# Zio_Qwiic_IO_Expander.net
KiCad netlist of a schematic drawn in EAGLE
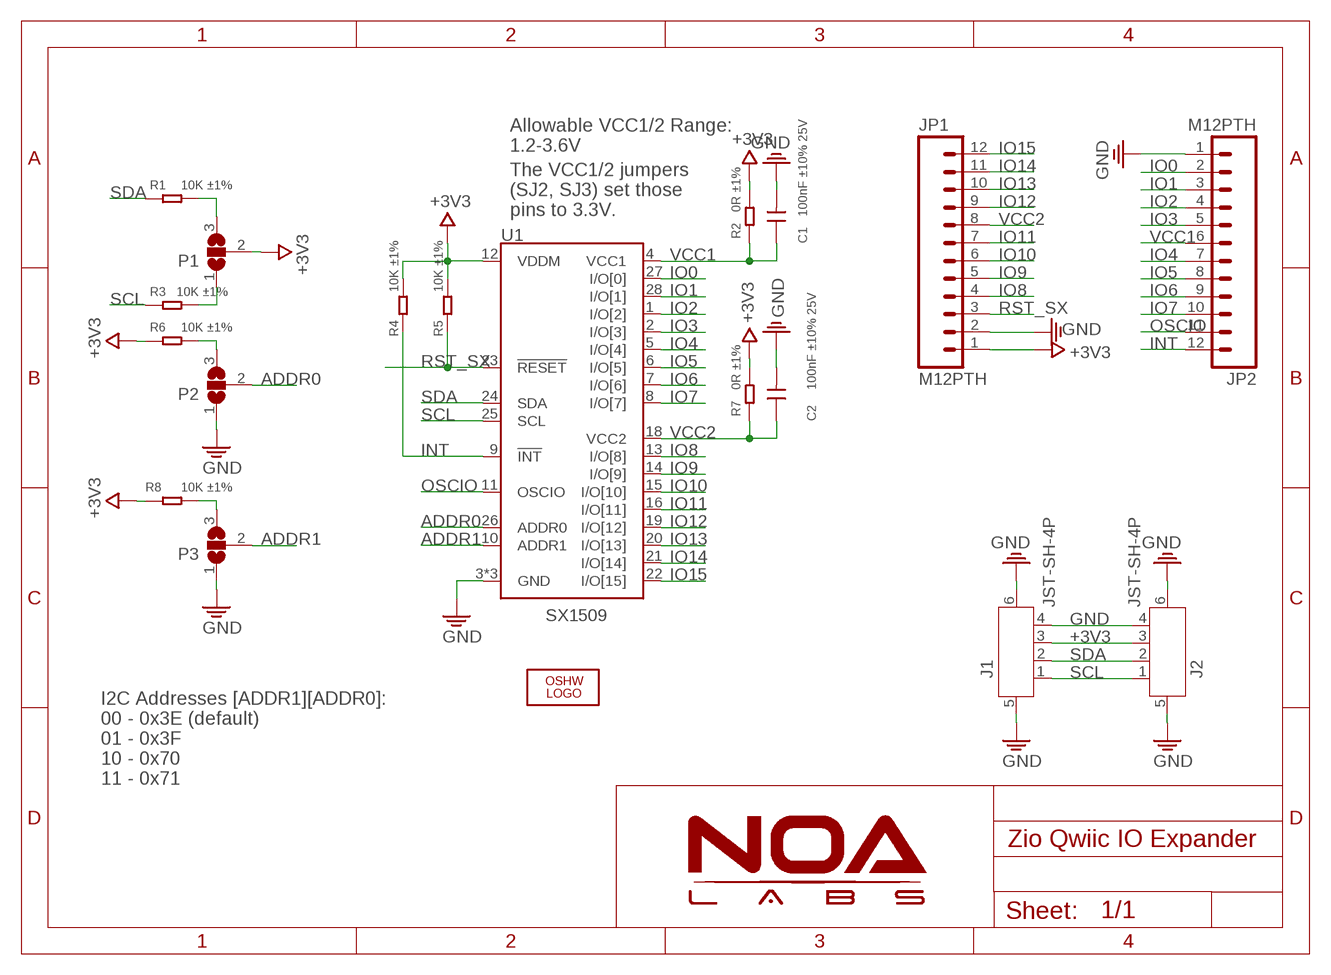
[diagram p0: schematic, sheet 1]

(export (version "E")
  (design (tool "Eeschema 10.0.6"))
  (components
    (comp (ref "C1")
      (value "100nF ±10% 25V")
      (footprint "eagle-import:0402")
      (libsource (lib "eagle-import") (part "C-0402"))
    )
    (comp (ref "C2")
      (value "100nF ±10% 25V")
      (footprint "eagle-import:0402")
      (libsource (lib "eagle-import") (part "C-0402"))
    )
    (comp (ref "J1")
      (value "JST-SH-4P")
      (footprint "eagle-import:JST-SH-4P-90")
      (libsource (lib "eagle-import") (part "JST-SH-4P"))
    )
    (comp (ref "J2")
      (value "JST-SH-4P")
      (footprint "eagle-import:JST-SH-4P-90")
      (libsource (lib "eagle-import") (part "JST-SH-4P"))
    )
    (comp (ref "JP1")
      (value "M12PTH")
      (footprint "eagle-import:1X12")
      (libsource (lib "eagle-import") (part "M12PTH"))
    )
    (comp (ref "JP2")
      (value "M12PTH")
      (footprint "eagle-import:1X12")
      (libsource (lib "eagle-import") (part "M12PTH"))
    )
    (comp (ref "LOGO")
      (value "LOGO-OSHW-6MILX0100-NT")
      (footprint "eagle-import:OSHW_6X100_NOTEXT")
      (libsource (lib "eagle-import") (part "LOGO-OSHW-6MILX0100-NT"))
    )
    (comp (ref "P1")
      (value "PAD-SOLDERJUMPER-2WAY")
      (footprint "eagle-import:3P-SMD-1.78X1.27")
      (libsource (lib "eagle-import") (part "PAD-SOLDERJUMPER-2WAY"))
    )
    (comp (ref "P2")
      (value "PAD-SOLDERJUMPER-2WAY")
      (footprint "eagle-import:3P-SMD-1.78X1.27")
      (libsource (lib "eagle-import") (part "PAD-SOLDERJUMPER-2WAY"))
    )
    (comp (ref "P3")
      (value "PAD-SOLDERJUMPER-2WAY")
      (footprint "eagle-import:3P-SMD-1.78X1.27")
      (libsource (lib "eagle-import") (part "PAD-SOLDERJUMPER-2WAY"))
    )
    (comp (ref "R1")
      (value "10K ±1%")
      (footprint "eagle-import:0402")
      (libsource (lib "eagle-import") (part "R-0402"))
    )
    (comp (ref "R2")
      (value "0R ±1%")
      (footprint "eagle-import:0402")
      (libsource (lib "eagle-import") (part "R-0402"))
    )
    (comp (ref "R3")
      (value "10K ±1%")
      (footprint "eagle-import:0402")
      (libsource (lib "eagle-import") (part "R-0402"))
    )
    (comp (ref "R4")
      (value "10K ±1%")
      (footprint "eagle-import:0402")
      (libsource (lib "eagle-import") (part "R-0402"))
    )
    (comp (ref "R5")
      (value "10K ±1%")
      (footprint "eagle-import:0402")
      (libsource (lib "eagle-import") (part "R-0402"))
    )
    (comp (ref "R6")
      (value "10K ±1%")
      (footprint "eagle-import:0402")
      (libsource (lib "eagle-import") (part "R-0402"))
    )
    (comp (ref "R7")
      (value "0R ±1%")
      (footprint "eagle-import:0402")
      (libsource (lib "eagle-import") (part "R-0402"))
    )
    (comp (ref "R8")
      (value "10K ±1%")
      (footprint "eagle-import:0402")
      (libsource (lib "eagle-import") (part "R-0402"))
    )
    (comp (ref "U1")
      (value "SX1509")
      (footprint "eagle-import:QFN-28")
      (libsource (lib "eagle-import") (part "SX1509"))
    )
  )
  (nets
    (net (code "1") (name "+3V3") (class "Default")
      (node (ref "J1") (pin "3") (pinfunction "3_3") (pintype "bidirectional"))
      (node (ref "J2") (pin "3") (pinfunction "3_3") (pintype "bidirectional"))
      (node (ref "JP1") (pin "1") (pinfunction "1_1") (pintype "passive"))
      (node (ref "P1") (pin "2") (pinfunction "2_2") (pintype "passive"))
      (node (ref "R2") (pin "2") (pinfunction "2_2") (pintype "passive"))
      (node (ref "R4") (pin "2") (pinfunction "2_2") (pintype "passive"))
      (node (ref "R5") (pin "2") (pinfunction "2_2") (pintype "passive"))
      (node (ref "R6") (pin "1") (pinfunction "1_1") (pintype "passive"))
      (node (ref "R7") (pin "2") (pinfunction "2_2") (pintype "passive"))
      (node (ref "R8") (pin "1") (pinfunction "1_1") (pintype "passive"))
      (node (ref "U1") (pin "12") (pinfunction "VDDM_12") (pintype "bidirectional"))
    )
    (net (code "2") (name "/ADDR0") (class "Default")
      (node (ref "P2") (pin "2") (pinfunction "2_2") (pintype "passive"))
      (node (ref "U1") (pin "26") (pinfunction "ADDR0_26") (pintype "bidirectional"))
    )
    (net (code "3") (name "/ADDR1") (class "Default")
      (node (ref "P3") (pin "2") (pinfunction "2_2") (pintype "passive"))
      (node (ref "U1") (pin "10") (pinfunction "ADDR1_10") (pintype "bidirectional"))
    )
    (net (code "4") (name "/INT") (class "Default")
      (node (ref "JP2") (pin "12") (pinfunction "12_12") (pintype "passive"))
      (node (ref "R4") (pin "1") (pinfunction "1_1") (pintype "passive"))
      (node (ref "U1") (pin "9") (pinfunction "~{INT}_9") (pintype "bidirectional"))
    )
    (net (code "5") (name "/IO0") (class "Default")
      (node (ref "JP2") (pin "2") (pinfunction "2_2") (pintype "passive"))
      (node (ref "U1") (pin "27") (pinfunction "I/O[0]_27") (pintype "bidirectional"))
    )
    (net (code "6") (name "/IO1") (class "Default")
      (node (ref "JP2") (pin "3") (pinfunction "3_3") (pintype "passive"))
      (node (ref "U1") (pin "28") (pinfunction "I/O[1]_28") (pintype "bidirectional"))
    )
    (net (code "7") (name "/IO2") (class "Default")
      (node (ref "JP2") (pin "4") (pinfunction "4_4") (pintype "passive"))
      (node (ref "U1") (pin "1") (pinfunction "I/O[2]_1") (pintype "bidirectional"))
    )
    (net (code "8") (name "/IO3") (class "Default")
      (node (ref "JP2") (pin "5") (pinfunction "5_5") (pintype "passive"))
      (node (ref "U1") (pin "2") (pinfunction "I/O[3]_2") (pintype "bidirectional"))
    )
    (net (code "9") (name "/IO4") (class "Default")
      (node (ref "JP2") (pin "7") (pinfunction "7_7") (pintype "passive"))
      (node (ref "U1") (pin "5") (pinfunction "I/O[4]_5") (pintype "bidirectional"))
    )
    (net (code "10") (name "/IO5") (class "Default")
      (node (ref "JP2") (pin "8") (pinfunction "8_8") (pintype "passive"))
      (node (ref "U1") (pin "6") (pinfunction "I/O[5]_6") (pintype "bidirectional"))
    )
    (net (code "11") (name "/IO6") (class "Default")
      (node (ref "JP2") (pin "9") (pinfunction "9_9") (pintype "passive"))
      (node (ref "U1") (pin "7") (pinfunction "I/O[6]_7") (pintype "bidirectional"))
    )
    (net (code "12") (name "/IO7") (class "Default")
      (node (ref "JP2") (pin "10") (pinfunction "10_10") (pintype "passive"))
      (node (ref "U1") (pin "8") (pinfunction "I/O[7]_8") (pintype "bidirectional"))
    )
    (net (code "13") (name "/IO8") (class "Default")
      (node (ref "JP1") (pin "4") (pinfunction "4_4") (pintype "passive"))
      (node (ref "U1") (pin "13") (pinfunction "I/O[8]_13") (pintype "bidirectional"))
    )
    (net (code "14") (name "/IO9") (class "Default")
      (node (ref "JP1") (pin "5") (pinfunction "5_5") (pintype "passive"))
      (node (ref "U1") (pin "14") (pinfunction "I/O[9]_14") (pintype "bidirectional"))
    )
    (net (code "15") (name "/IO10") (class "Default")
      (node (ref "JP1") (pin "6") (pinfunction "6_6") (pintype "passive"))
      (node (ref "U1") (pin "15") (pinfunction "I/O[10]_15") (pintype "bidirectional"))
    )
    (net (code "16") (name "/IO11") (class "Default")
      (node (ref "JP1") (pin "7") (pinfunction "7_7") (pintype "passive"))
      (node (ref "U1") (pin "16") (pinfunction "I/O[11]_16") (pintype "bidirectional"))
    )
    (net (code "17") (name "/IO12") (class "Default")
      (node (ref "JP1") (pin "9") (pinfunction "9_9") (pintype "passive"))
      (node (ref "U1") (pin "19") (pinfunction "I/O[12]_19") (pintype "bidirectional"))
    )
    (net (code "18") (name "/IO13") (class "Default")
      (node (ref "JP1") (pin "10") (pinfunction "10_10") (pintype "passive"))
      (node (ref "U1") (pin "20") (pinfunction "I/O[13]_20") (pintype "bidirectional"))
    )
    (net (code "19") (name "/IO14") (class "Default")
      (node (ref "JP1") (pin "11") (pinfunction "11_11") (pintype "passive"))
      (node (ref "U1") (pin "21") (pinfunction "I/O[14]_21") (pintype "bidirectional"))
    )
    (net (code "20") (name "/IO15") (class "Default")
      (node (ref "JP1") (pin "12") (pinfunction "12_12") (pintype "passive"))
      (node (ref "U1") (pin "22") (pinfunction "I/O[15]_22") (pintype "bidirectional"))
    )
    (net (code "21") (name "/OSCIO") (class "Default")
      (node (ref "JP2") (pin "11") (pinfunction "11_11") (pintype "passive"))
      (node (ref "U1") (pin "11") (pinfunction "OSCIO_11") (pintype "bidirectional"))
    )
    (net (code "22") (name "/RST_SX") (class "Default")
      (node (ref "JP1") (pin "3") (pinfunction "3_3") (pintype "passive"))
      (node (ref "R5") (pin "1") (pinfunction "1_1") (pintype "passive"))
      (node (ref "U1") (pin "23") (pinfunction "~{RESET}_23") (pintype "bidirectional"))
    )
    (net (code "23") (name "/SCL") (class "Default")
      (node (ref "J1") (pin "1") (pinfunction "1_1") (pintype "bidirectional"))
      (node (ref "J2") (pin "1") (pinfunction "1_1") (pintype "bidirectional"))
      (node (ref "R3") (pin "1") (pinfunction "1_1") (pintype "passive"))
      (node (ref "U1") (pin "25") (pinfunction "SCL_25") (pintype "bidirectional"))
    )
    (net (code "24") (name "/SDA") (class "Default")
      (node (ref "J1") (pin "2") (pinfunction "2_2") (pintype "bidirectional"))
      (node (ref "J2") (pin "2") (pinfunction "2_2") (pintype "bidirectional"))
      (node (ref "R1") (pin "1") (pinfunction "1_1") (pintype "passive"))
      (node (ref "U1") (pin "24") (pinfunction "SDA_24") (pintype "bidirectional"))
    )
    (net (code "25") (name "/VCC1") (class "Default")
      (node (ref "C1") (pin "1") (pinfunction "1_1") (pintype "passive"))
      (node (ref "JP2") (pin "6") (pinfunction "6_6") (pintype "passive"))
      (node (ref "R2") (pin "1") (pinfunction "1_1") (pintype "passive"))
      (node (ref "U1") (pin "4") (pinfunction "VCC1_4") (pintype "bidirectional"))
    )
    (net (code "26") (name "/VCC2") (class "Default")
      (node (ref "C2") (pin "1") (pinfunction "1_1") (pintype "passive"))
      (node (ref "JP1") (pin "8") (pinfunction "8_8") (pintype "passive"))
      (node (ref "R7") (pin "1") (pinfunction "1_1") (pintype "passive"))
      (node (ref "U1") (pin "18") (pinfunction "VCC2_18") (pintype "bidirectional"))
    )
    (net (code "27") (name "GND") (class "Default")
      (node (ref "C1") (pin "2") (pinfunction "2_2") (pintype "passive"))
      (node (ref "C2") (pin "2") (pinfunction "2_2") (pintype "passive"))
      (node (ref "J1") (pin "4") (pinfunction "4_4") (pintype "bidirectional"))
      (node (ref "J1") (pin "5") (pinfunction "5_5") (pintype "bidirectional"))
      (node (ref "J1") (pin "6") (pinfunction "6_6") (pintype "bidirectional"))
      (node (ref "J2") (pin "4") (pinfunction "4_4") (pintype "bidirectional"))
      (node (ref "J2") (pin "5") (pinfunction "5_5") (pintype "bidirectional"))
      (node (ref "J2") (pin "6") (pinfunction "6_6") (pintype "bidirectional"))
      (node (ref "JP1") (pin "2") (pinfunction "2_2") (pintype "passive"))
      (node (ref "JP2") (pin "1") (pinfunction "1_1") (pintype "passive"))
      (node (ref "P2") (pin "1") (pinfunction "1_1") (pintype "passive"))
      (node (ref "P3") (pin "1") (pinfunction "1_1") (pintype "passive"))
      (node (ref "U1") (pin "17") (pinfunction "GND_17") (pintype "bidirectional"))
      (node (ref "U1") (pin "29") (pinfunction "GND_29") (pintype "bidirectional"))
      (node (ref "U1") (pin "3") (pinfunction "GND_3") (pintype "bidirectional"))
    )
    (net (code "28") (name "Net-(P1-Pad1)") (class "Default")
      (node (ref "P1") (pin "1") (pinfunction "1_1") (pintype "passive"))
      (node (ref "R3") (pin "2") (pinfunction "2_2") (pintype "passive"))
    )
    (net (code "29") (name "Net-(P1-Pad3)") (class "Default")
      (node (ref "P1") (pin "3") (pinfunction "3_3") (pintype "passive"))
      (node (ref "R1") (pin "2") (pinfunction "2_2") (pintype "passive"))
    )
    (net (code "30") (name "Net-(P2-Pad3)") (class "Default")
      (node (ref "P2") (pin "3") (pinfunction "3_3") (pintype "passive"))
      (node (ref "R6") (pin "2") (pinfunction "2_2") (pintype "passive"))
    )
    (net (code "31") (name "Net-(P3-Pad3)") (class "Default")
      (node (ref "P3") (pin "3") (pinfunction "3_3") (pintype "passive"))
      (node (ref "R8") (pin "2") (pinfunction "2_2") (pintype "passive"))
    )
  )
)
